# main_board.net
KiCad netlist of a schematic drawn in EAGLE
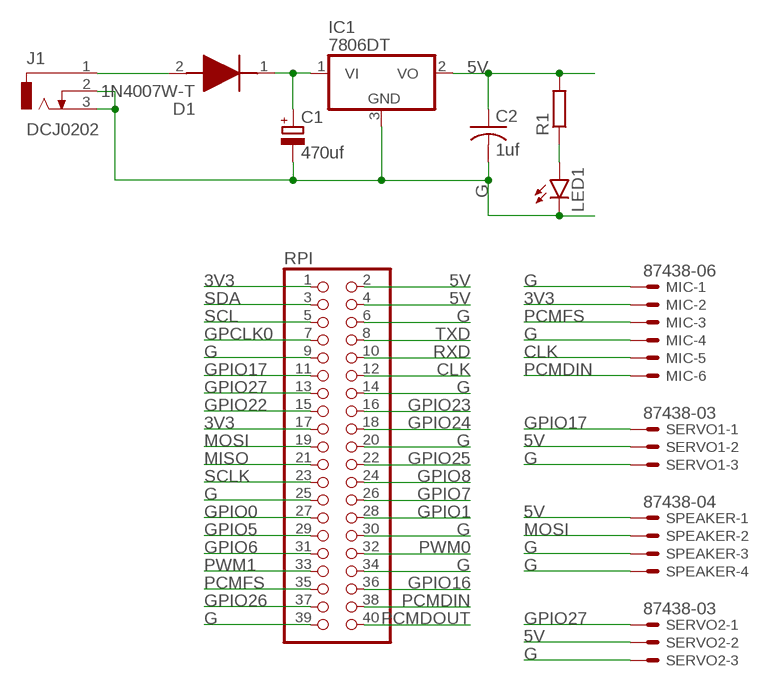
[diagram p0: schematic, sheet 1]

(export (version "E")
  (design (tool "Eeschema 10.0.6"))
  (components
    (comp (ref "C1")
      (value "470uf")
      (footprint "eagle-import:PANASONIC_D")
      (libsource (lib "eagle-import") (part "CPOL-EUD"))
    )
    (comp (ref "C2")
      (value "1uf")
      (footprint "eagle-import:C0805")
      (libsource (lib "eagle-import") (part "C-USC0805"))
    )
    (comp (ref "D1")
      (value "1N4007W-T")
      (footprint "eagle-import:SODFL3818X130N")
      (fields (field (name "MOUSER_PART_NUMBER") "583-1N4007W-T"))
      (libsource (lib "eagle-import") (part "1N4007W-T"))
    )
    (comp (ref "IC1")
      (value "7806DT")
      (footprint "eagle-import:TO252")
      (libsource (lib "eagle-import") (part "78DT06"))
    )
    (comp (ref "J1")
      (value "DCJ0202")
      (footprint "eagle-import:DCJ0202")
      (libsource (lib "eagle-import") (part "DCJ0202"))
    )
    (comp (ref "LED1")
      (value "LEDCHIP-LED0805")
      (footprint "eagle-import:CHIP-LED0805")
      (libsource (lib "eagle-import") (part "LEDCHIP-LED0805"))
    )
    (comp (ref "MIC")
      (value "87438-06")
      (footprint "eagle-import:87438-06")
      (fields (field (name "MF") "MOLEX") (field (name "MPN") "87438-0643"))
      (libsource (lib "eagle-import") (part "87438-06"))
    )
    (comp (ref "R1")
      (value "R-EU_R0603")
      (footprint "eagle-import:R0603")
      (libsource (lib "eagle-import") (part "R-EU_R0603"))
    )
    (comp (ref "RPI")
      (value "PINHD-2X20")
      (footprint "eagle-import:2X20")
      (libsource (lib "eagle-import") (part "PINHD-2X20"))
    )
    (comp (ref "SERVO1")
      (value "87438-03")
      (footprint "eagle-import:87438-03")
      (fields (field (name "MF") "MOLEX"))
      (libsource (lib "eagle-import") (part "87438-03"))
    )
    (comp (ref "SERVO2")
      (value "87438-03")
      (footprint "eagle-import:87438-03")
      (fields (field (name "MF") "MOLEX"))
      (libsource (lib "eagle-import") (part "87438-03"))
    )
    (comp (ref "SPEAKER")
      (value "87438-04")
      (footprint "eagle-import:87438-04")
      (fields (field (name "MF") "MOLEX"))
      (libsource (lib "eagle-import") (part "87438-04"))
    )
  )
  (nets
    (net (code "1") (name "/3V3") (class "Default")
      (node (ref "MIC") (pin "2") (pinfunction "S_2") (pintype "passive"))
      (node (ref "RPI") (pin "1") (pinfunction "1_1") (pintype "passive"))
      (node (ref "RPI") (pin "17") (pinfunction "17_17") (pintype "passive"))
    )
    (net (code "2") (name "/5V") (class "Default")
      (node (ref "C2") (pin "1") (pinfunction "1_1") (pintype "passive"))
      (node (ref "IC1") (pin "2") (pinfunction "VO_2") (pintype "passive"))
      (node (ref "R1") (pin "2") (pinfunction "2_2") (pintype "passive"))
      (node (ref "RPI") (pin "2") (pinfunction "2_2") (pintype "passive"))
      (node (ref "RPI") (pin "4") (pinfunction "4_4") (pintype "passive"))
      (node (ref "SERVO1") (pin "2") (pinfunction "S_2") (pintype "passive"))
      (node (ref "SERVO2") (pin "2") (pinfunction "S_2") (pintype "passive"))
      (node (ref "SPEAKER") (pin "1") (pinfunction "S_1") (pintype "passive"))
    )
    (net (code "3") (name "/CLK") (class "Default")
      (node (ref "MIC") (pin "5") (pinfunction "S_5") (pintype "passive"))
      (node (ref "RPI") (pin "12") (pinfunction "12_12") (pintype "passive"))
    )
    (net (code "4") (name "/G") (class "Default")
      (node (ref "C1") (pin "-") (pinfunction "-_-") (pintype "passive"))
      (node (ref "C2") (pin "2") (pinfunction "2_2") (pintype "passive"))
      (node (ref "IC1") (pin "3") (pinfunction "GND_3") (pintype "passive"))
      (node (ref "J1") (pin "2") (pinfunction "2_2") (pintype "passive"))
      (node (ref "J1") (pin "3") (pinfunction "3_3") (pintype "passive"))
      (node (ref "LED1") (pin "C") (pinfunction "C_C") (pintype "passive"))
      (node (ref "MIC") (pin "1") (pinfunction "S_1") (pintype "passive"))
      (node (ref "MIC") (pin "4") (pinfunction "S_4") (pintype "passive"))
      (node (ref "RPI") (pin "14") (pinfunction "14_14") (pintype "passive"))
      (node (ref "RPI") (pin "20") (pinfunction "20_20") (pintype "passive"))
      (node (ref "RPI") (pin "25") (pinfunction "25_25") (pintype "passive"))
      (node (ref "RPI") (pin "30") (pinfunction "30_30") (pintype "passive"))
      (node (ref "RPI") (pin "34") (pinfunction "34_34") (pintype "passive"))
      (node (ref "RPI") (pin "39") (pinfunction "39_39") (pintype "passive"))
      (node (ref "RPI") (pin "6") (pinfunction "6_6") (pintype "passive"))
      (node (ref "RPI") (pin "9") (pinfunction "9_9") (pintype "passive"))
      (node (ref "SERVO1") (pin "3") (pinfunction "S_3") (pintype "passive"))
      (node (ref "SERVO2") (pin "3") (pinfunction "S_3") (pintype "passive"))
      (node (ref "SPEAKER") (pin "3") (pinfunction "S_3") (pintype "passive"))
      (node (ref "SPEAKER") (pin "4") (pinfunction "S_4") (pintype "passive"))
    )
    (net (code "5") (name "/GPCLK0") (class "Default")
      (node (ref "RPI") (pin "7") (pinfunction "7_7") (pintype "passive"))
    )
    (net (code "6") (name "/GPIO0") (class "Default")
      (node (ref "RPI") (pin "27") (pinfunction "27_27") (pintype "passive"))
    )
    (net (code "7") (name "/GPIO1") (class "Default")
      (node (ref "RPI") (pin "28") (pinfunction "28_28") (pintype "passive"))
    )
    (net (code "8") (name "/GPIO5") (class "Default")
      (node (ref "RPI") (pin "29") (pinfunction "29_29") (pintype "passive"))
    )
    (net (code "9") (name "/GPIO6") (class "Default")
      (node (ref "RPI") (pin "31") (pinfunction "31_31") (pintype "passive"))
    )
    (net (code "10") (name "/GPIO7") (class "Default")
      (node (ref "RPI") (pin "26") (pinfunction "26_26") (pintype "passive"))
    )
    (net (code "11") (name "/GPIO8") (class "Default")
      (node (ref "RPI") (pin "24") (pinfunction "24_24") (pintype "passive"))
    )
    (net (code "12") (name "/GPIO16") (class "Default")
      (node (ref "RPI") (pin "36") (pinfunction "36_36") (pintype "passive"))
    )
    (net (code "13") (name "/GPIO17") (class "Default")
      (node (ref "RPI") (pin "11") (pinfunction "11_11") (pintype "passive"))
      (node (ref "SERVO1") (pin "1") (pinfunction "S_1") (pintype "passive"))
    )
    (net (code "14") (name "/GPIO22") (class "Default")
      (node (ref "RPI") (pin "15") (pinfunction "15_15") (pintype "passive"))
    )
    (net (code "15") (name "/GPIO23") (class "Default")
      (node (ref "RPI") (pin "16") (pinfunction "16_16") (pintype "passive"))
    )
    (net (code "16") (name "/GPIO24") (class "Default")
      (node (ref "RPI") (pin "18") (pinfunction "18_18") (pintype "passive"))
    )
    (net (code "17") (name "/GPIO25") (class "Default")
      (node (ref "RPI") (pin "22") (pinfunction "22_22") (pintype "passive"))
    )
    (net (code "18") (name "/GPIO26") (class "Default")
      (node (ref "RPI") (pin "37") (pinfunction "37_37") (pintype "passive"))
    )
    (net (code "19") (name "/GPIO27") (class "Default")
      (node (ref "RPI") (pin "13") (pinfunction "13_13") (pintype "passive"))
      (node (ref "SERVO2") (pin "1") (pinfunction "S_1") (pintype "passive"))
    )
    (net (code "20") (name "/MISO") (class "Default")
      (node (ref "RPI") (pin "21") (pinfunction "21_21") (pintype "passive"))
    )
    (net (code "21") (name "/MOSI") (class "Default")
      (node (ref "RPI") (pin "19") (pinfunction "19_19") (pintype "passive"))
      (node (ref "SPEAKER") (pin "2") (pinfunction "S_2") (pintype "passive"))
    )
    (net (code "22") (name "/PCMDIN") (class "Default")
      (node (ref "MIC") (pin "6") (pinfunction "S_6") (pintype "passive"))
      (node (ref "RPI") (pin "38") (pinfunction "38_38") (pintype "passive"))
    )
    (net (code "23") (name "/PCMDOUT") (class "Default")
      (node (ref "RPI") (pin "40") (pinfunction "40_40") (pintype "passive"))
    )
    (net (code "24") (name "/PCMFS") (class "Default")
      (node (ref "MIC") (pin "3") (pinfunction "S_3") (pintype "passive"))
      (node (ref "RPI") (pin "35") (pinfunction "35_35") (pintype "passive"))
    )
    (net (code "25") (name "/PWM0") (class "Default")
      (node (ref "RPI") (pin "32") (pinfunction "32_32") (pintype "passive"))
    )
    (net (code "26") (name "/PWM1") (class "Default")
      (node (ref "RPI") (pin "33") (pinfunction "33_33") (pintype "passive"))
    )
    (net (code "27") (name "/RXD") (class "Default")
      (node (ref "RPI") (pin "10") (pinfunction "10_10") (pintype "passive"))
    )
    (net (code "28") (name "/SCL") (class "Default")
      (node (ref "RPI") (pin "5") (pinfunction "5_5") (pintype "passive"))
    )
    (net (code "29") (name "/SCLK") (class "Default")
      (node (ref "RPI") (pin "23") (pinfunction "23_23") (pintype "passive"))
    )
    (net (code "30") (name "/SDA") (class "Default")
      (node (ref "RPI") (pin "3") (pinfunction "3_3") (pintype "passive"))
    )
    (net (code "31") (name "/TXD") (class "Default")
      (node (ref "RPI") (pin "8") (pinfunction "8_8") (pintype "passive"))
    )
    (net (code "32") (name "Net-(D1-A)") (class "Default")
      (node (ref "D1") (pin "2") (pinfunction "A_2") (pintype "bidirectional"))
      (node (ref "J1") (pin "1") (pinfunction "1_1") (pintype "passive"))
    )
    (net (code "33") (name "Net-(D1-K)") (class "Default")
      (node (ref "C1") (pin "+") (pinfunction "+_+") (pintype "passive"))
      (node (ref "D1") (pin "1") (pinfunction "K_1") (pintype "bidirectional"))
      (node (ref "IC1") (pin "1") (pinfunction "VI_1") (pintype "input"))
    )
    (net (code "34") (name "Net-(LED1-PadA)") (class "Default")
      (node (ref "LED1") (pin "A") (pinfunction "A_A") (pintype "passive"))
      (node (ref "R1") (pin "1") (pinfunction "1_1") (pintype "passive"))
    )
  )
)
